# Power_1.net
KiCad netlist of a schematic drawn in Altium Designer
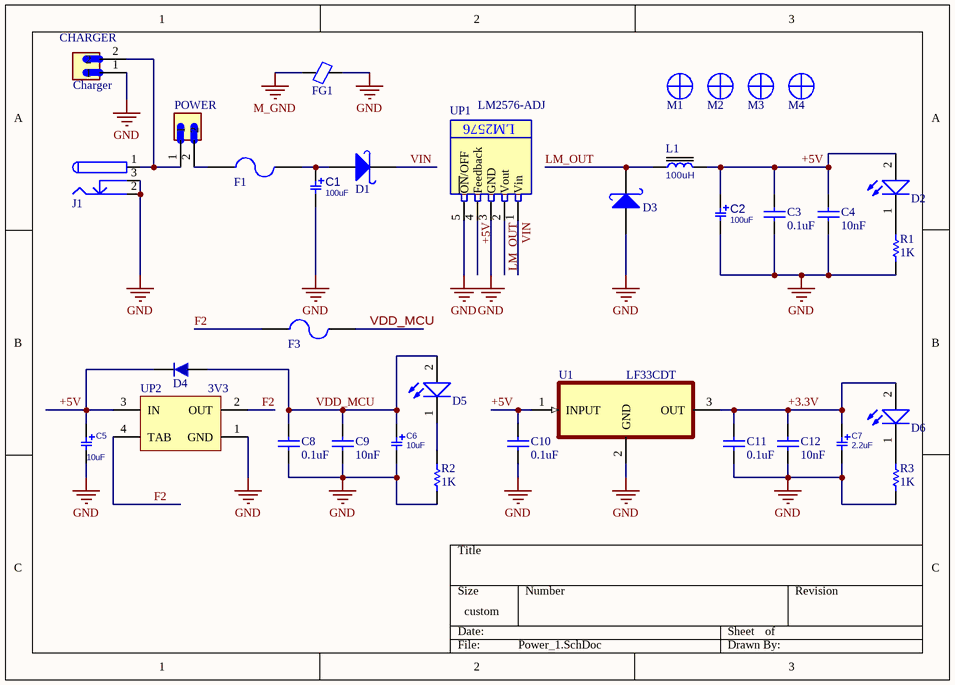
[diagram p0: Power_1.SchDoc]

(export (version "E")
  (design (tool "Eeschema 10.0.6"))
  (components
    (comp (ref "C1")
      (value "100uF")
      (footprint "C_EL_10_10")
      (description "CAP, THD, ELEC,")
      (fields (field (name "MANF_P#") "MANF_PART#") (field (name "MANF") "MANF"))
      (libsource (lib "Passive") (part "CAP_SMD_EL"))
    )
    (comp (ref "C2")
      (value "100uF")
      (footprint "C_EL_10_10")
      (description "CAP, THD, ELEC,")
      (fields (field (name "MANF_P#") "MANF_PART#") (field (name "MANF") "MANF"))
      (libsource (lib "Passive") (part "CAP_SMD_EL"))
    )
    (comp (ref "C3")
      (value "0.1uF")
      (footprint "CAPC3413X12N")
      (description "CAP 0805")
      (fields (field (name "DESIGNER") "Abbas Basereh"))
      (libsource (lib "Altium") (part "CAP SMD 0805"))
    )
    (comp (ref "C4")
      (value "10nF")
      (footprint "CAPC3413X12N")
      (description "CAP 0805")
      (fields (field (name "DESIGNER") "Abbas Basereh"))
      (libsource (lib "Altium") (part "CAP SMD 0805"))
    )
    (comp (ref "C5")
      (value "10uF")
      (footprint "C_TN_6032")
      (description "CAP, SMD, TAN,")
      (libsource (lib "Passive") (part "CAP_SMD_TAN"))
    )
    (comp (ref "C6")
      (value "10uF")
      (footprint "C_TN_6032")
      (description "CAP, SMD, TAN,")
      (libsource (lib "Passive") (part "CAP_SMD_TAN"))
    )
    (comp (ref "C7")
      (value "2.2uF")
      (footprint "C_TN_6032")
      (description "CAP, SMD, TAN,")
      (libsource (lib "Passive") (part "CAP_SMD_TAN"))
    )
    (comp (ref "C8")
      (value "0.1uF")
      (footprint "CAPC3413X12N")
      (description "CAP 0805")
      (fields (field (name "DESIGNER") "Abbas Basereh"))
      (libsource (lib "Altium") (part "CAP SMD 0805"))
    )
    (comp (ref "C9")
      (value "10nF")
      (footprint "CAPC3413X12N")
      (description "CAP 0805")
      (fields (field (name "DESIGNER") "Abbas Basereh"))
      (libsource (lib "Altium") (part "CAP SMD 0805"))
    )
    (comp (ref "C10")
      (value "0.1uF")
      (footprint "CAPC3413X12N")
      (description "CAP 0805")
      (fields (field (name "DESIGNER") "Abbas Basereh"))
      (libsource (lib "Altium") (part "CAP SMD 0805"))
    )
    (comp (ref "C11")
      (value "0.1uF")
      (footprint "CAPC3413X12N")
      (description "CAP 0805")
      (fields (field (name "DESIGNER") "Abbas Basereh"))
      (libsource (lib "Altium") (part "CAP SMD 0805"))
    )
    (comp (ref "C12")
      (value "10nF")
      (footprint "CAPC3413X12N")
      (description "CAP 0805")
      (fields (field (name "DESIGNER") "Abbas Basereh"))
      (libsource (lib "Altium") (part "CAP SMD 0805"))
    )
    (comp (ref "CHARGER")
      (value "Charger")
      (footprint "JST_B2P-VH(LF)(SN)")
      (description "Connector Header Through Hole 2 position 0.156 (3.96mm)")
      (fields (field (name "MP") "B2P-VH(LF)(SN)") (field (name "MF") "JST Sales"))
      (libsource (lib "B2P-VH_LF__SN_") (part "B2P-VH(LF)(SN)"))
    )
    (comp (ref "D1")
      (value "1n5822")
      (footprint "DO-214AB(SMC)")
      (description "Schottky Rectifiers")
      (fields
        (field (name "MANUFACTURER") "ON Semiconductor/Fairchild")
        (field (name "DESIGNER") "Abbas Basereh")
      )
      (libsource (lib "Altium") (part "1N5822 SMD"))
    )
    (comp (ref "D2")
      (value "LED SMD PACKAGE")
      (footprint "LED_SMD_0805")
      (description "SMD Mono-color Chip LED Waterclear")
      (fields (field (name "PART NUMBER") "150080BS75000") (field (name "PUBLISHER") "Ali Hafizi"))
      (libsource (lib "Altium") (part "LED SMD PACKAGE"))
    )
    (comp (ref "D3")
      (value "1n5822")
      (footprint "DO-214AB(SMC)")
      (description "Schottky Rectifiers")
      (fields
        (field (name "MANUFACTURER") "ON Semiconductor/Fairchild")
        (field (name "DESIGNER") "Abbas Basereh")
      )
      (libsource (lib "Altium") (part "1N5822 SMD"))
    )
    (comp (ref "D4")
      (value "1n4007")
      (footprint "DIOM4629X24N")
      (description "Standard Rectifiers")
      (fields (field (name "MANUFACTURER") "DC COMPONENTS") (field (name "DESIGNER") "Abbas Basereh"))
      (libsource (lib "Altium") (part "1n4007 SMD M7"))
    )
    (comp (ref "D5")
      (value "LED SMD PACKAGE")
      (footprint "LED_SMD_0805")
      (description "SMD Mono-color Chip LED Waterclear")
      (fields (field (name "PART NUMBER") "150080BS75000") (field (name "PUBLISHER") "Ali Hafizi"))
      (libsource (lib "Altium") (part "LED SMD PACKAGE"))
    )
    (comp (ref "D6")
      (value "LED SMD PACKAGE")
      (footprint "LED_SMD_0805")
      (description "SMD Mono-color Chip LED Waterclear")
      (fields (field (name "PART NUMBER") "150080BS75000") (field (name "PUBLISHER") "Ali Hafizi"))
      (libsource (lib "Altium") (part "LED SMD PACKAGE"))
    )
    (comp (ref "F1")
      (value "F=3A")
      (footprint "1206 FUSE")
      (description "SMD Fuses 1206")
      (fields (field (name "DESIGNER") "Abbas Basereh"))
      (libsource (lib "Altium") (part "Fuse SMD1206"))
    )
    (comp (ref "F3")
      (value "F=3A")
      (footprint "1206 FUSE")
      (description "SMD Fuses 1206")
      (fields (field (name "DESIGNER") "Abbas Basereh"))
      (libsource (lib "Altium") (part "Fuse SMD1206"))
    )
    (comp (ref "FG1")
      (value "Ferrite Bead SMD")
      (footprint "FB0805")
      (fields (field (name "DESIGNER") "Ali Hafizi"))
      (libsource (lib "Altium") (part "Ferrite Bead SMD Package"))
    )
    (comp (ref "J1")
      (value "DC Power Jack")
      (footprint "DC Power Jack 1")
      (description "DC Power Jack. Center Pin 2.5mm. Diameter: 5.7mm")
      (fields (field (name "DESIGNER") "Ali Hafizi"))
      (libsource (lib "Altium") (part "DC Power Jack"))
    )
    (comp (ref "L1")
      (value "100uH")
      (footprint "L_12")
      (description "INDUCTOR, POWER, SMD")
      (libsource (lib "Passive") (part "INDPWR_SMD"))
    )
    (comp (ref "M1")
      (value "Screw")
      (footprint "Board Screw 3mm")
      (description "Board Screw With Spacer")
      (libsource (lib "Altium") (part "Board Screw 3MM"))
    )
    (comp (ref "M2")
      (value "Screw")
      (footprint "Board Screw 3mm")
      (description "Board Screw With Spacer")
      (libsource (lib "Altium") (part "Board Screw 3MM"))
    )
    (comp (ref "M3")
      (value "Screw")
      (footprint "Board Screw 3mm")
      (description "Board Screw With Spacer")
      (libsource (lib "Altium") (part "Board Screw 3MM"))
    )
    (comp (ref "M4")
      (value "Screw")
      (footprint "Board Screw 3mm")
      (description "Board Screw With Spacer")
      (libsource (lib "Altium") (part "Board Screw 3MM"))
    )
    (comp (ref "POWER")
      (value "B2P-VH(LF)(SN)")
      (footprint "JST_B2P-VH(LF)(SN)")
      (description "Connector Header Through Hole 2 position 0.156 (3.96mm)")
      (fields (field (name "MF") "JST Sales"))
      (libsource (lib "") (part "B2P-VH(LF)(SN)_1"))
    )
    (comp (ref "R1")
      (value "1K")
      (footprint "RESC3413X04N")
      (description "RES 0805")
      (fields (field (name "DESIGNER") "Abbas Basereh"))
      (libsource (lib "Altium") (part "RES 0805 0.125W"))
    )
    (comp (ref "R2")
      (value "1K")
      (footprint "RESC3413X04N")
      (description "RES 0805")
      (fields (field (name "DESIGNER") "Abbas Basereh"))
      (libsource (lib "Altium") (part "RES 0805 0.125W"))
    )
    (comp (ref "R3")
      (value "1K")
      (footprint "RESC3413X04N")
      (description "RES 0805")
      (fields (field (name "DESIGNER") "Abbas Basereh"))
      (libsource (lib "Altium") (part "RES 0805 0.125W"))
    )
    (comp (ref "U1")
      (value "LF33CDT")
      (footprint "TO228P972X240-3N")
      (description "Linear Voltage Regulator IC Positive Fixed 1 Output 500mA DPAK")
      (fields (field (name "MF") "STMicroelectronics"))
      (libsource (lib "LF33CDT") (part "LF33CDT"))
    )
    (comp (ref "UP1")
      (value "LM2576-ADJ")
      (footprint "LM2576 SMD")
      (description "1.2-50V, 3A variable output step-down switching voltage regulator")
      (fields (field (name "DESIGNER") "Abbas Basereh"))
      (libsource (lib "Altium") (part "LM2576-Adj"))
    )
    (comp (ref "UP2")
      (value "3V3")
      (footprint "SOT223")
      (description "x.x Volt, 800mA Low-Dropout Linear Regulator, 4-pin SOT-223")
      (fields (field (name "DESIGNER") "Ali Hafizi"))
      (libsource (lib "Altium") (part "AMS1117-x.x"))
    )
  )
  (nets
    (net (code "1") (name "/+3.3V") (class "Default")
      (node (ref "C11") (pin "2") (pinfunction "2_2") (pintype "passive"))
      (node (ref "C12") (pin "2") (pinfunction "2_2") (pintype "passive"))
      (node (ref "C7") (pin "1") (pinfunction "1_1") (pintype "passive"))
      (node (ref "D6") (pin "2") (pinfunction "A_2") (pintype "passive"))
      (node (ref "U1") (pin "3") (pinfunction "OUT_3") (pintype "power_in"))
    )
    (net (code "2") (name "/+5V") (class "Default")
      (node (ref "C10") (pin "2") (pinfunction "2_2") (pintype "passive"))
      (node (ref "C2") (pin "1") (pinfunction "1_1") (pintype "passive"))
      (node (ref "C3") (pin "2") (pinfunction "2_2") (pintype "passive"))
      (node (ref "C4") (pin "2") (pinfunction "2_2") (pintype "passive"))
      (node (ref "C5") (pin "1") (pinfunction "1_1") (pintype "passive"))
      (node (ref "D2") (pin "2") (pinfunction "A_2") (pintype "passive"))
      (node (ref "D4") (pin "2") (pintype "passive"))
      (node (ref "L1") (pin "2") (pinfunction "2_2") (pintype "passive"))
      (node (ref "U1") (pin "1") (pinfunction "INPUT_1") (pintype "input"))
      (node (ref "UP1") (pin "4") (pinfunction "Feedback_4") (pintype "passive"))
      (node (ref "UP2") (pin "3") (pinfunction "IN_3") (pintype "power_in"))
    )
    (net (code "3") (name "/F2") (class "Default")
      (node (ref "F3") (pin "1") (pinfunction "1_1") (pintype "passive"))
      (node (ref "UP2") (pin "2") (pinfunction "OUT_2") (pintype "power_in"))
      (node (ref "UP2") (pin "4") (pinfunction "TAB_4") (pintype "power_in"))
    )
    (net (code "4") (name "/LM_OUT") (class "Default")
      (node (ref "D3") (pin "2") (pinfunction "K_2") (pintype "passive"))
      (node (ref "L1") (pin "1") (pinfunction "1_1") (pintype "passive"))
      (node (ref "UP1") (pin "2") (pinfunction "Vout_2") (pintype "power_in"))
    )
    (net (code "5") (name "/VDD_MCU") (class "Default")
      (node (ref "C6") (pin "1") (pinfunction "1_1") (pintype "passive"))
      (node (ref "C8") (pin "2") (pinfunction "2_2") (pintype "passive"))
      (node (ref "C9") (pin "2") (pinfunction "2_2") (pintype "passive"))
      (node (ref "D4") (pin "1") (pintype "passive"))
      (node (ref "D5") (pin "2") (pinfunction "A_2") (pintype "passive"))
      (node (ref "F3") (pin "2") (pinfunction "2_2") (pintype "passive"))
    )
    (net (code "6") (name "/VIN") (class "Default")
      (node (ref "D1") (pin "2") (pinfunction "K_2") (pintype "passive"))
      (node (ref "UP1") (pin "1") (pinfunction "Vin_1") (pintype "power_in"))
    )
    (net (code "7") (name "GND") (class "Default")
      (node (ref "C1") (pin "2") (pinfunction "2_2") (pintype "passive"))
      (node (ref "C10") (pin "1") (pinfunction "1_1") (pintype "passive"))
      (node (ref "C11") (pin "1") (pinfunction "1_1") (pintype "passive"))
      (node (ref "C12") (pin "1") (pinfunction "1_1") (pintype "passive"))
      (node (ref "C2") (pin "2") (pinfunction "2_2") (pintype "passive"))
      (node (ref "C3") (pin "1") (pinfunction "1_1") (pintype "passive"))
      (node (ref "C4") (pin "1") (pinfunction "1_1") (pintype "passive"))
      (node (ref "C5") (pin "2") (pinfunction "2_2") (pintype "passive"))
      (node (ref "C6") (pin "2") (pinfunction "2_2") (pintype "passive"))
      (node (ref "C7") (pin "2") (pinfunction "2_2") (pintype "passive"))
      (node (ref "C8") (pin "1") (pinfunction "1_1") (pintype "passive"))
      (node (ref "C9") (pin "1") (pinfunction "1_1") (pintype "passive"))
      (node (ref "CHARGER") (pin "1") (pinfunction "1_1") (pintype "passive"))
      (node (ref "D3") (pin "1") (pinfunction "A_1") (pintype "passive"))
      (node (ref "FG1") (pin "2") (pinfunction "2_2") (pintype "passive"))
      (node (ref "J1") (pin "2") (pinfunction "2_2") (pintype "power_in"))
      (node (ref "J1") (pin "3") (pinfunction "3_3") (pintype "power_in"))
      (node (ref "R1") (pin "1") (pinfunction "1_1") (pintype "passive"))
      (node (ref "R2") (pin "1") (pinfunction "1_1") (pintype "passive"))
      (node (ref "R3") (pin "1") (pinfunction "1_1") (pintype "passive"))
      (node (ref "U1") (pin "2") (pinfunction "GND_2") (pintype "passive"))
      (node (ref "UP1") (pin "3") (pinfunction "GND_3") (pintype "power_in"))
      (node (ref "UP1") (pin "5") (pinfunction "~{ON}/OFF_5") (pintype "passive"))
      (node (ref "UP2") (pin "1") (pinfunction "GND_1") (pintype "power_in"))
    )
    (net (code "8") (name "M_GND") (class "Default")
      (node (ref "FG1") (pin "1") (pinfunction "1_1") (pintype "passive"))
    )
    (net (code "9") (name "Net-(CHARGER-Pad2)") (class "Default")
      (node (ref "CHARGER") (pin "2") (pinfunction "2_2") (pintype "passive"))
      (node (ref "J1") (pin "1") (pinfunction "1_1") (pintype "power_in"))
      (node (ref "POWER") (pin "1") (pinfunction "1_1") (pintype "passive"))
    )
    (net (code "10") (name "Net-(D1-A)") (class "Default")
      (node (ref "C1") (pin "1") (pinfunction "1_1") (pintype "passive"))
      (node (ref "D1") (pin "1") (pinfunction "A_1") (pintype "passive"))
      (node (ref "F1") (pin "2") (pinfunction "2_2") (pintype "passive"))
    )
    (net (code "11") (name "Net-(D2-K)") (class "Default")
      (node (ref "D2") (pin "1") (pinfunction "K_1") (pintype "passive"))
      (node (ref "R1") (pin "2") (pinfunction "2_2") (pintype "passive"))
    )
    (net (code "12") (name "Net-(D5-K)") (class "Default")
      (node (ref "D5") (pin "1") (pinfunction "K_1") (pintype "passive"))
      (node (ref "R2") (pin "2") (pinfunction "2_2") (pintype "passive"))
    )
    (net (code "13") (name "Net-(D6-K)") (class "Default")
      (node (ref "D6") (pin "1") (pinfunction "K_1") (pintype "passive"))
      (node (ref "R3") (pin "2") (pinfunction "2_2") (pintype "passive"))
    )
    (net (code "14") (name "Net-(F1-Pad1)") (class "Default")
      (node (ref "F1") (pin "1") (pinfunction "1_1") (pintype "passive"))
      (node (ref "POWER") (pin "2") (pinfunction "2_2") (pintype "passive"))
    )
  )
)
